# 2101-210806300163-_-.net
KiCad netlist of a schematic drawn in Altium Designer
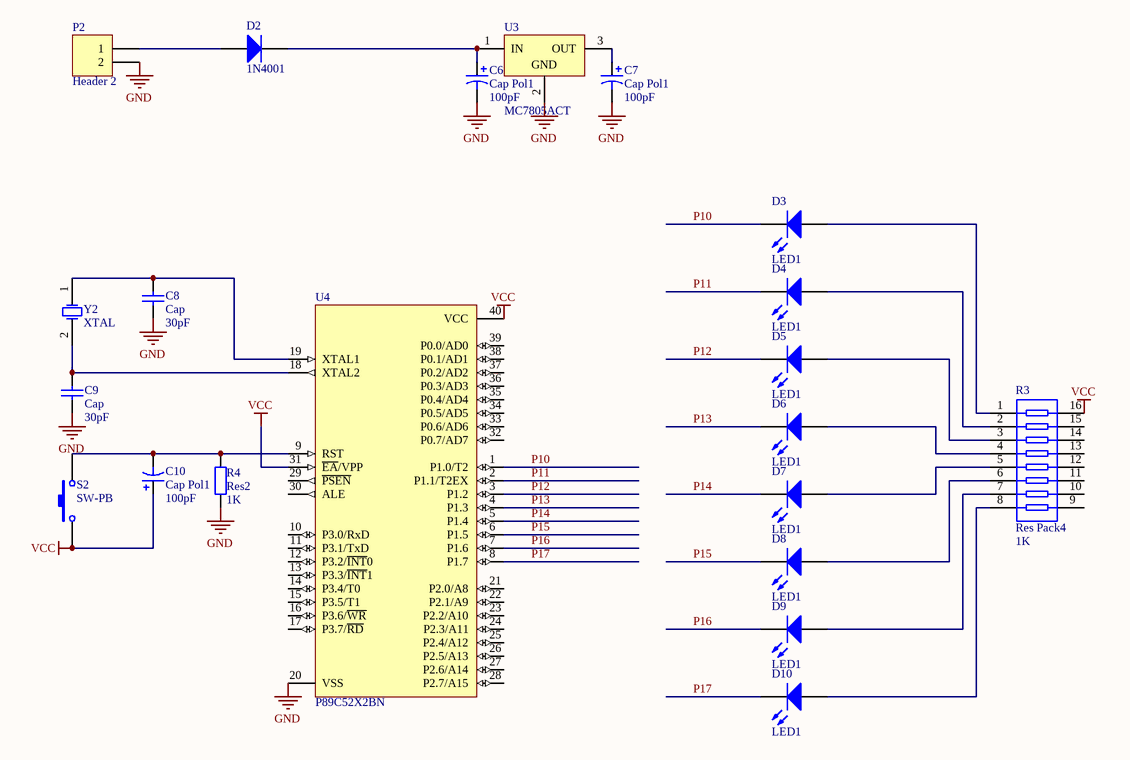
[diagram p0: 通信工程(专升本)2101-210806300163-李烨攀-单片机控制流水灯电路.SchDoc]

(export (version "E")
  (design (tool "Eeschema 10.0.6"))
  (components
    (comp (ref "C6")
      (value "Cap Pol1")
      (footprint "RB7.6-15")
      (description "Polarized Capacitor (Radial)")
      (fields (field (name "ALTIUM_VALUE") "100pF") (field (name "PUBLISHER") "Altium Limited"))
      (libsource (lib "Miscellaneous Devices") (part "Cap Pol1"))
    )
    (comp (ref "C7")
      (value "Cap Pol1")
      (footprint "RB7.6-15")
      (description "Polarized Capacitor (Radial)")
      (fields (field (name "ALTIUM_VALUE") "100pF") (field (name "PUBLISHER") "Altium Limited"))
      (libsource (lib "Miscellaneous Devices") (part "Cap Pol1"))
    )
    (comp (ref "C8")
      (value "Cap")
      (footprint "RAD-0.3")
      (description "Capacitor")
      (fields (field (name "ALTIUM_VALUE") "30pF") (field (name "PUBLISHER") "Altium Limited"))
      (libsource (lib "Miscellaneous Devices") (part "Cap"))
    )
    (comp (ref "C9")
      (value "Cap")
      (footprint "RAD-0.3")
      (description "Capacitor")
      (fields (field (name "ALTIUM_VALUE") "30pF") (field (name "PUBLISHER") "Altium Limited"))
      (libsource (lib "Miscellaneous Devices") (part "Cap"))
    )
    (comp (ref "C10")
      (value "Cap Pol1")
      (footprint "RB7.6-15")
      (description "Polarized Capacitor (Radial)")
      (fields (field (name "ALTIUM_VALUE") "100pF") (field (name "PUBLISHER") "Altium Limited"))
      (libsource (lib "Miscellaneous Devices") (part "Cap Pol1"))
    )
    (comp (ref "D2")
      (value "1N4001")
      (footprint "DO-41")
      (description "1.0 Ampere General Purpose Rectifier")
      (fields (field (name "PUBLISHER") "Altium Limited"))
      (libsource (lib "FSC Discrete Rectifier") (part "1N4001"))
    )
    (comp (ref "D3")
      (value "LED1")
      (footprint "LED-1")
      (description "Typical RED GaAs LED")
      (fields (field (name "PUBLISHER") "Altium Limited"))
      (libsource (lib "Miscellaneous Devices") (part "LED1"))
    )
    (comp (ref "D4")
      (value "LED1")
      (footprint "LED-1")
      (description "Typical RED GaAs LED")
      (fields (field (name "PUBLISHER") "Altium Limited"))
      (libsource (lib "Miscellaneous Devices") (part "LED1"))
    )
    (comp (ref "D5")
      (value "LED1")
      (footprint "LED-1")
      (description "Typical RED GaAs LED")
      (fields (field (name "PUBLISHER") "Altium Limited"))
      (libsource (lib "Miscellaneous Devices") (part "LED1"))
    )
    (comp (ref "D6")
      (value "LED1")
      (footprint "LED-1")
      (description "Typical RED GaAs LED")
      (fields (field (name "PUBLISHER") "Altium Limited"))
      (libsource (lib "Miscellaneous Devices") (part "LED1"))
    )
    (comp (ref "D7")
      (value "LED1")
      (footprint "LED-1")
      (description "Typical RED GaAs LED")
      (fields (field (name "PUBLISHER") "Altium Limited"))
      (libsource (lib "Miscellaneous Devices") (part "LED1"))
    )
    (comp (ref "D8")
      (value "LED1")
      (footprint "LED-1")
      (description "Typical RED GaAs LED")
      (fields (field (name "PUBLISHER") "Altium Limited"))
      (libsource (lib "Miscellaneous Devices") (part "LED1"))
    )
    (comp (ref "D9")
      (value "LED1")
      (footprint "LED-1")
      (description "Typical RED GaAs LED")
      (fields (field (name "PUBLISHER") "Altium Limited"))
      (libsource (lib "Miscellaneous Devices") (part "LED1"))
    )
    (comp (ref "D10")
      (value "LED1")
      (footprint "LED-1")
      (description "Typical RED GaAs LED")
      (fields (field (name "PUBLISHER") "Altium Limited"))
      (libsource (lib "Miscellaneous Devices") (part "LED1"))
    )
    (comp (ref "P2")
      (value "Header 2")
      (footprint "HDR1X2")
      (description "Header, 2-Pin")
      (fields (field (name "PUBLISHER") "Altium Limited"))
      (libsource (lib "Miscellaneous Connectors") (part "Header 2"))
    )
    (comp (ref "R3")
      (value "Res Pack4")
      (footprint "SSOP16_N")
      (description "Isolated Resistor Network")
      (fields (field (name "ALTIUM_VALUE") "1K") (field (name "PUBLISHER") "Altium Limited"))
      (libsource (lib "Miscellaneous Devices") (part "Res Pack4"))
    )
    (comp (ref "R4")
      (value "Res2")
      (footprint "AXIAL-0.4")
      (description "Resistor")
      (fields (field (name "ALTIUM_VALUE") "1K") (field (name "PUBLISHER") "Altium Limited"))
      (libsource (lib "Miscellaneous Devices") (part "Res2"))
    )
    (comp (ref "S2")
      (value "SW-PB")
      (footprint "SPST-2")
      (description "Switch")
      (fields (field (name "PUBLISHER") "Altium Limited"))
      (libsource (lib "Miscellaneous Devices") (part "SW-PB"))
    )
    (comp (ref "U3")
      (value "MC7805ACT")
      (footprint "221A-04")
      (description "3-Terminal Positive Fixed Voltage Regulator")
      (fields (field (name "PUBLISHER") "Altium Limited"))
      (libsource (lib "Motorola Power Mgt Voltage Regulator") (part "MC7805ACT"))
    )
    (comp (ref "U4")
      (value "P89C52X2BN")
      (footprint "SOT129-1")
      (description "80C51 8-Bit Flash Microcontroller Family, 8 kB Flash")
      (fields (field (name "PUBLISHER") "Altium Limited"))
      (libsource (lib "Philips Microcontroller 8-Bit") (part "P89C52X2BN"))
    )
    (comp (ref "Y2")
      (value "XTAL")
      (footprint "R38")
      (description "Crystal Oscillator")
      (fields (field (name "PUBLISHER") "Altium Limited"))
      (libsource (lib "Miscellaneous Devices") (part "XTAL"))
    )
  )
  (nets
    (net (code "1") (name "/P10") (class "Default")
      (node (ref "D3") (pin "2") (pinfunction "K_2") (pintype "passive"))
      (node (ref "U4") (pin "1") (pinfunction "P1.0/T2_1") (pintype "bidirectional"))
    )
    (net (code "2") (name "/P11") (class "Default")
      (node (ref "D4") (pin "2") (pinfunction "K_2") (pintype "passive"))
      (node (ref "U4") (pin "2") (pinfunction "P1.1/T2EX_2") (pintype "bidirectional"))
    )
    (net (code "3") (name "/P12") (class "Default")
      (node (ref "D5") (pin "2") (pinfunction "K_2") (pintype "passive"))
      (node (ref "U4") (pin "3") (pinfunction "P1.2_3") (pintype "bidirectional"))
    )
    (net (code "4") (name "/P13") (class "Default")
      (node (ref "D6") (pin "2") (pinfunction "K_2") (pintype "passive"))
      (node (ref "U4") (pin "4") (pinfunction "P1.3_4") (pintype "bidirectional"))
    )
    (net (code "5") (name "/P14") (class "Default")
      (node (ref "D7") (pin "2") (pinfunction "K_2") (pintype "passive"))
      (node (ref "U4") (pin "5") (pinfunction "P1.4_5") (pintype "bidirectional"))
    )
    (net (code "6") (name "/P15") (class "Default")
      (node (ref "D8") (pin "2") (pinfunction "K_2") (pintype "passive"))
      (node (ref "U4") (pin "6") (pinfunction "P1.5_6") (pintype "bidirectional"))
    )
    (net (code "7") (name "/P16") (class "Default")
      (node (ref "D9") (pin "2") (pinfunction "K_2") (pintype "passive"))
      (node (ref "U4") (pin "7") (pinfunction "P1.6_7") (pintype "bidirectional"))
    )
    (net (code "8") (name "/P17") (class "Default")
      (node (ref "D10") (pin "2") (pinfunction "K_2") (pintype "passive"))
      (node (ref "U4") (pin "8") (pinfunction "P1.7_8") (pintype "bidirectional"))
    )
    (net (code "9") (name "GND") (class "Default")
      (node (ref "C6") (pin "2") (pinfunction "2_2") (pintype "passive"))
      (node (ref "C7") (pin "2") (pinfunction "2_2") (pintype "passive"))
      (node (ref "C8") (pin "1") (pinfunction "1_1") (pintype "passive"))
      (node (ref "C9") (pin "1") (pinfunction "1_1") (pintype "passive"))
      (node (ref "P2") (pin "2") (pinfunction "2_2") (pintype "passive"))
      (node (ref "R4") (pin "1") (pinfunction "1_1") (pintype "passive"))
      (node (ref "U3") (pin "2") (pinfunction "GND_2") (pintype "power_in"))
      (node (ref "U4") (pin "20") (pinfunction "VSS_20") (pintype "power_in"))
    )
    (net (code "10") (name "Net-(D2-A)") (class "Default")
      (node (ref "D2") (pin "1") (pinfunction "A_1") (pintype "passive"))
      (node (ref "P2") (pin "1") (pinfunction "1_1") (pintype "passive"))
    )
    (net (code "11") (name "Net-(D2-K)") (class "Default")
      (node (ref "C6") (pin "1") (pinfunction "1_1") (pintype "passive"))
      (node (ref "D2") (pin "2") (pinfunction "K_2") (pintype "passive"))
      (node (ref "U3") (pin "1") (pinfunction "IN_1") (pintype "power_in"))
    )
    (net (code "12") (name "Net-(D3-A)") (class "Default")
      (node (ref "D3") (pin "1") (pinfunction "A_1") (pintype "passive"))
      (node (ref "R3") (pin "1") (pinfunction "1_1") (pintype "passive"))
    )
    (net (code "13") (name "Net-(D4-A)") (class "Default")
      (node (ref "D4") (pin "1") (pinfunction "A_1") (pintype "passive"))
      (node (ref "R3") (pin "2") (pinfunction "2_2") (pintype "passive"))
    )
    (net (code "14") (name "Net-(D5-A)") (class "Default")
      (node (ref "D5") (pin "1") (pinfunction "A_1") (pintype "passive"))
      (node (ref "R3") (pin "3") (pinfunction "3_3") (pintype "passive"))
    )
    (net (code "15") (name "Net-(D6-A)") (class "Default")
      (node (ref "D6") (pin "1") (pinfunction "A_1") (pintype "passive"))
      (node (ref "R3") (pin "4") (pinfunction "4_4") (pintype "passive"))
    )
    (net (code "16") (name "Net-(D7-A)") (class "Default")
      (node (ref "D7") (pin "1") (pinfunction "A_1") (pintype "passive"))
      (node (ref "R3") (pin "5") (pinfunction "5_5") (pintype "passive"))
    )
    (net (code "17") (name "Net-(D8-A)") (class "Default")
      (node (ref "D8") (pin "1") (pinfunction "A_1") (pintype "passive"))
      (node (ref "R3") (pin "6") (pinfunction "6_6") (pintype "passive"))
    )
    (net (code "18") (name "Net-(D9-A)") (class "Default")
      (node (ref "D9") (pin "1") (pinfunction "A_1") (pintype "passive"))
      (node (ref "R3") (pin "7") (pinfunction "7_7") (pintype "passive"))
    )
    (net (code "19") (name "Net-(D10-A)") (class "Default")
      (node (ref "D10") (pin "1") (pinfunction "A_1") (pintype "passive"))
      (node (ref "R3") (pin "8") (pinfunction "8_8") (pintype "passive"))
    )
    (net (code "20") (name "Net-(U3-OUT)") (class "Default")
      (node (ref "C7") (pin "1") (pinfunction "1_1") (pintype "passive"))
      (node (ref "U3") (pin "3") (pinfunction "OUT_3") (pintype "power_in"))
    )
    (net (code "21") (name "Net-(U4-RST)") (class "Default")
      (node (ref "C10") (pin "2") (pinfunction "2_2") (pintype "passive"))
      (node (ref "R4") (pin "2") (pinfunction "2_2") (pintype "passive"))
      (node (ref "S2") (pin "2") (pinfunction "2_2") (pintype "passive"))
      (node (ref "U4") (pin "9") (pinfunction "RST_9") (pintype "input"))
    )
    (net (code "22") (name "Net-(U4-XTAL1)") (class "Default")
      (node (ref "C8") (pin "2") (pinfunction "2_2") (pintype "passive"))
      (node (ref "U4") (pin "19") (pinfunction "XTAL1_19") (pintype "input"))
      (node (ref "Y2") (pin "1") (pinfunction "OSC1_1") (pintype "passive"))
    )
    (net (code "23") (name "Net-(U4-XTAL2)") (class "Default")
      (node (ref "C9") (pin "2") (pinfunction "2_2") (pintype "passive"))
      (node (ref "U4") (pin "18") (pinfunction "XTAL2_18") (pintype "output"))
      (node (ref "Y2") (pin "2") (pinfunction "OSC2_2") (pintype "passive"))
    )
    (net (code "24") (name "VCC") (class "Default")
      (node (ref "C10") (pin "1") (pinfunction "1_1") (pintype "passive"))
      (node (ref "R3") (pin "16") (pinfunction "16_16") (pintype "passive"))
      (node (ref "S2") (pin "1") (pinfunction "1_1") (pintype "passive"))
      (node (ref "U4") (pin "31") (pinfunction "~{EA}/VPP_31") (pintype "input"))
      (node (ref "U4") (pin "40") (pinfunction "VCC_40") (pintype "power_in"))
    )
    (net (code "25") (name "unconnected-(R3-Pad9)") (class "Default")
      (node (ref "R3") (pin "9") (pinfunction "9_9") (pintype "passive"))
    )
    (net (code "26") (name "unconnected-(R3-Pad10)") (class "Default")
      (node (ref "R3") (pin "10") (pinfunction "10_10") (pintype "passive"))
    )
    (net (code "27") (name "unconnected-(R3-Pad11)") (class "Default")
      (node (ref "R3") (pin "11") (pinfunction "11_11") (pintype "passive"))
    )
    (net (code "28") (name "unconnected-(R3-Pad12)") (class "Default")
      (node (ref "R3") (pin "12") (pinfunction "12_12") (pintype "passive"))
    )
    (net (code "29") (name "unconnected-(R3-Pad13)") (class "Default")
      (node (ref "R3") (pin "13") (pinfunction "13_13") (pintype "passive"))
    )
    (net (code "30") (name "unconnected-(R3-Pad14)") (class "Default")
      (node (ref "R3") (pin "14") (pinfunction "14_14") (pintype "passive"))
    )
    (net (code "31") (name "unconnected-(R3-Pad15)") (class "Default")
      (node (ref "R3") (pin "15") (pinfunction "15_15") (pintype "passive"))
    )
    (net (code "32") (name "unconnected-(U4-ALE-Pad30)") (class "Default")
      (node (ref "U4") (pin "30") (pinfunction "ALE_30") (pintype "output"))
    )
    (net (code "33") (name "unconnected-(U4-P0.0{slash}AD0-Pad39)") (class "Default")
      (node (ref "U4") (pin "39") (pinfunction "P0.0/AD0_39") (pintype "bidirectional"))
    )
    (net (code "34") (name "unconnected-(U4-P0.1{slash}AD1-Pad38)") (class "Default")
      (node (ref "U4") (pin "38") (pinfunction "P0.1/AD1_38") (pintype "bidirectional"))
    )
    (net (code "35") (name "unconnected-(U4-P0.2{slash}AD2-Pad37)") (class "Default")
      (node (ref "U4") (pin "37") (pinfunction "P0.2/AD2_37") (pintype "bidirectional"))
    )
    (net (code "36") (name "unconnected-(U4-P0.3{slash}AD3-Pad36)") (class "Default")
      (node (ref "U4") (pin "36") (pinfunction "P0.3/AD3_36") (pintype "bidirectional"))
    )
    (net (code "37") (name "unconnected-(U4-P0.4{slash}AD4-Pad35)") (class "Default")
      (node (ref "U4") (pin "35") (pinfunction "P0.4/AD4_35") (pintype "bidirectional"))
    )
    (net (code "38") (name "unconnected-(U4-P0.5{slash}AD5-Pad34)") (class "Default")
      (node (ref "U4") (pin "34") (pinfunction "P0.5/AD5_34") (pintype "bidirectional"))
    )
    (net (code "39") (name "unconnected-(U4-P0.6{slash}AD6-Pad33)") (class "Default")
      (node (ref "U4") (pin "33") (pinfunction "P0.6/AD6_33") (pintype "bidirectional"))
    )
    (net (code "40") (name "unconnected-(U4-P0.7{slash}AD7-Pad32)") (class "Default")
      (node (ref "U4") (pin "32") (pinfunction "P0.7/AD7_32") (pintype "bidirectional"))
    )
    (net (code "41") (name "unconnected-(U4-P2.0{slash}A8-Pad21)") (class "Default")
      (node (ref "U4") (pin "21") (pinfunction "P2.0/A8_21") (pintype "bidirectional"))
    )
    (net (code "42") (name "unconnected-(U4-P2.1{slash}A9-Pad22)") (class "Default")
      (node (ref "U4") (pin "22") (pinfunction "P2.1/A9_22") (pintype "bidirectional"))
    )
    (net (code "43") (name "unconnected-(U4-P2.2{slash}A10-Pad23)") (class "Default")
      (node (ref "U4") (pin "23") (pinfunction "P2.2/A10_23") (pintype "bidirectional"))
    )
    (net (code "44") (name "unconnected-(U4-P2.3{slash}A11-Pad24)") (class "Default")
      (node (ref "U4") (pin "24") (pinfunction "P2.3/A11_24") (pintype "bidirectional"))
    )
    (net (code "45") (name "unconnected-(U4-P2.4{slash}A12-Pad25)") (class "Default")
      (node (ref "U4") (pin "25") (pinfunction "P2.4/A12_25") (pintype "bidirectional"))
    )
    (net (code "46") (name "unconnected-(U4-P2.5{slash}A13-Pad26)") (class "Default")
      (node (ref "U4") (pin "26") (pinfunction "P2.5/A13_26") (pintype "bidirectional"))
    )
    (net (code "47") (name "unconnected-(U4-P2.6{slash}A14-Pad27)") (class "Default")
      (node (ref "U4") (pin "27") (pinfunction "P2.6/A14_27") (pintype "bidirectional"))
    )
    (net (code "48") (name "unconnected-(U4-P2.7{slash}A15-Pad28)") (class "Default")
      (node (ref "U4") (pin "28") (pinfunction "P2.7/A15_28") (pintype "bidirectional"))
    )
    (net (code "49") (name "unconnected-(U4-P3.0{slash}RxD-Pad10)") (class "Default")
      (node (ref "U4") (pin "10") (pinfunction "P3.0/RxD_10") (pintype "bidirectional"))
    )
    (net (code "50") (name "unconnected-(U4-P3.1{slash}TxD-Pad11)") (class "Default")
      (node (ref "U4") (pin "11") (pinfunction "P3.1/TxD_11") (pintype "bidirectional"))
    )
    (net (code "51") (name "unconnected-(U4-P3.2{slash}~{INT}0-Pad12)") (class "Default")
      (node (ref "U4") (pin "12") (pinfunction "P3.2/~{INT}0_12") (pintype "bidirectional"))
    )
    (net (code "52") (name "unconnected-(U4-P3.3{slash}~{INT}1-Pad13)") (class "Default")
      (node (ref "U4") (pin "13") (pinfunction "P3.3/~{INT}1_13") (pintype "bidirectional"))
    )
    (net (code "53") (name "unconnected-(U4-P3.4{slash}T0-Pad14)") (class "Default")
      (node (ref "U4") (pin "14") (pinfunction "P3.4/T0_14") (pintype "bidirectional"))
    )
    (net (code "54") (name "unconnected-(U4-P3.5{slash}T1-Pad15)") (class "Default")
      (node (ref "U4") (pin "15") (pinfunction "P3.5/T1_15") (pintype "bidirectional"))
    )
    (net (code "55") (name "unconnected-(U4-P3.6{slash}~{WR}-Pad16)") (class "Default")
      (node (ref "U4") (pin "16") (pinfunction "P3.6/~{WR}_16") (pintype "bidirectional"))
    )
    (net (code "56") (name "unconnected-(U4-P3.7{slash}~{RD}-Pad17)") (class "Default")
      (node (ref "U4") (pin "17") (pinfunction "P3.7/~{RD}_17") (pintype "bidirectional"))
    )
    (net (code "57") (name "unconnected-(U4-~{PSEN}-Pad29)") (class "Default")
      (node (ref "U4") (pin "29") (pinfunction "~{PSEN}_29") (pintype "output"))
    )
  )
)
